# Sensor_module.net
KiCad netlist of a schematic drawn in EAGLE
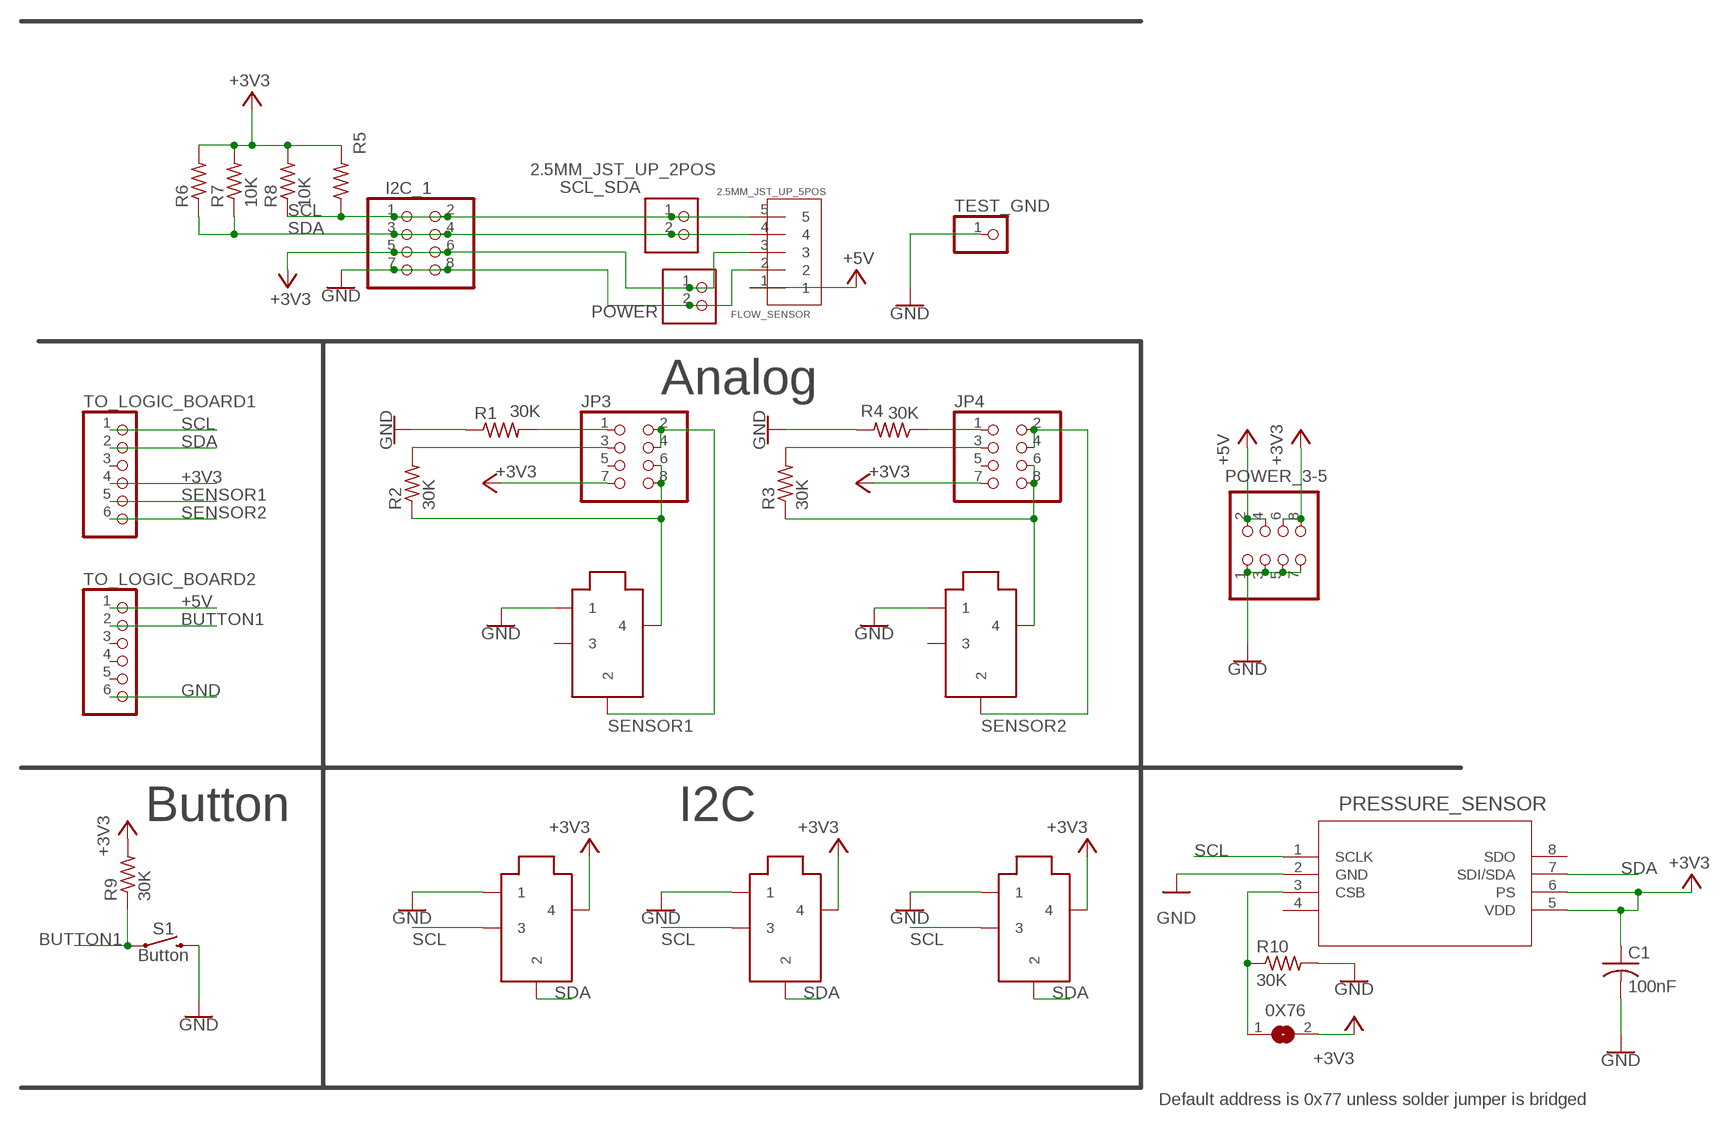
[diagram p0: schematic, sheet 1]

(export (version "E")
  (design (tool "Eeschema 10.0.6"))
  (components
    (comp (ref "0X76")
      (value "SJ")
      (footprint "eagle-import:SJ")
      (libsource (lib "eagle-import") (part "SJ"))
    )
    (comp (ref "ANALOG1")
      (value "AUDIOJACK_2.5MM_SMD")
      (footprint "eagle-import:AJ_2.5_SMD")
      (libsource (lib "eagle-import") (part "AUDIOJACK_2.5MM_SMD"))
    )
    (comp (ref "ANALOG2")
      (value "AUDIOJACK_2.5MM_SMD")
      (footprint "eagle-import:AJ_2.5_SMD")
      (libsource (lib "eagle-import") (part "AUDIOJACK_2.5MM_SMD"))
    )
    (comp (ref "C1")
      (value "100nF")
      (footprint "eagle-import:C1206")
      (libsource (lib "eagle-import") (part "C-USC1206"))
    )
    (comp (ref "FLOW_SENSOR")
      (value "2.5MM_JST_UP_5POS")
      (footprint "eagle-import:JST_5POS_2.5MM_UP")
      (libsource (lib "eagle-import") (part "2.5MM_JST_UP_5POS"))
    )
    (comp (ref "I2C_1")
      (value "PINHD-2X4")
      (footprint "eagle-import:2X04")
      (libsource (lib "eagle-import") (part "PINHD-2X4"))
    )
    (comp (ref "JP3")
      (value "PINHD-2X4")
      (footprint "eagle-import:2X04")
      (libsource (lib "eagle-import") (part "PINHD-2X4"))
    )
    (comp (ref "JP4")
      (value "PINHD-2X4")
      (footprint "eagle-import:2X04")
      (libsource (lib "eagle-import") (part "PINHD-2X4"))
    )
    (comp (ref "POWER")
      (value "2.5MM_JST_UP_2POS")
      (footprint "eagle-import:JST_2POS_2.5MM_UP")
      (libsource (lib "eagle-import") (part "2.5MM_JST_UP_2POS"))
    )
    (comp (ref "POWER_3-5")
      (value "PINHD-2X4")
      (footprint "eagle-import:2X04")
      (libsource (lib "eagle-import") (part "PINHD-2X4"))
    )
    (comp (ref "PRESSURE_SENSOR")
      (value "MS580302BA01-00")
      (footprint "eagle-import:MS5803-02BA01")
      (fields (field (name "MANUFACTURER_PART_NUMBER") "MS580302BA0100"))
      (libsource (lib "eagle-import") (part "MS580302BA01-00"))
    )
    (comp (ref "R1")
      (value "30K")
      (footprint "eagle-import:R1206")
      (libsource (lib "eagle-import") (part "R-US_R1206"))
    )
    (comp (ref "R2")
      (value "30K")
      (footprint "eagle-import:R1206")
      (libsource (lib "eagle-import") (part "R-US_R1206"))
    )
    (comp (ref "R3")
      (value "30K")
      (footprint "eagle-import:R1206")
      (libsource (lib "eagle-import") (part "R-US_R1206"))
    )
    (comp (ref "R4")
      (value "30K")
      (footprint "eagle-import:R1206")
      (libsource (lib "eagle-import") (part "R-US_R1206"))
    )
    (comp (ref "R5")
      (value "R-US_R1206")
      (footprint "eagle-import:R1206")
      (libsource (lib "eagle-import") (part "R-US_R1206"))
    )
    (comp (ref "R6")
      (value "R-US_R1206")
      (footprint "eagle-import:R1206")
      (libsource (lib "eagle-import") (part "R-US_R1206"))
    )
    (comp (ref "R7")
      (value "10K")
      (footprint "eagle-import:0204_7")
      (libsource (lib "eagle-import") (part "R-US_0204/7"))
    )
    (comp (ref "R8")
      (value "10K")
      (footprint "eagle-import:0204_7")
      (libsource (lib "eagle-import") (part "R-US_0204/7"))
    )
    (comp (ref "R9")
      (value "30K")
      (footprint "eagle-import:R1206")
      (libsource (lib "eagle-import") (part "R-US_R1206"))
    )
    (comp (ref "R10")
      (value "30K")
      (footprint "eagle-import:R1206")
      (libsource (lib "eagle-import") (part "R-US_R1206"))
    )
    (comp (ref "S1")
      (value "Button")
      (footprint "eagle-import:TACTILE_SWITCH_PTH_6.0MM")
      (libsource (lib "eagle-import") (part "MOMENTARY-SWITCH-SPST-PTH-6.0MM"))
    )
    (comp (ref "SCL_SDA")
      (value "2.5MM_JST_UP_2POS")
      (footprint "eagle-import:JST_2POS_2.5MM_UP")
      (libsource (lib "eagle-import") (part "2.5MM_JST_UP_2POS"))
    )
    (comp (ref "TEST_GND")
      (value "PINHD-1X1")
      (footprint "eagle-import:1X01")
      (libsource (lib "eagle-import") (part "PINHD-1X1"))
    )
    (comp (ref "TO_LOGIC_BOARD1")
      (value "PINHD-1X6CB")
      (footprint "eagle-import:1X06-CLEANBIG")
      (libsource (lib "eagle-import") (part "PINHD-1X6CB"))
    )
    (comp (ref "TO_LOGIC_BOARD2")
      (value "PINHD-1X6CB")
      (footprint "eagle-import:1X06-CLEANBIG")
      (libsource (lib "eagle-import") (part "PINHD-1X6CB"))
    )
    (comp (ref "U$1")
      (value "I2C")
      (footprint "eagle-import:AJ_2.5_SMD")
      (libsource (lib "eagle-import") (part "AUDIOJACK_2.5MM_SMD"))
    )
    (comp (ref "U$2")
      (value "I2C")
      (footprint "eagle-import:AJ_2.5_SMD")
      (libsource (lib "eagle-import") (part "AUDIOJACK_2.5MM_SMD"))
    )
    (comp (ref "U$5")
      (value "I2C")
      (footprint "eagle-import:AJ_2.5_SMD")
      (libsource (lib "eagle-import") (part "AUDIOJACK_2.5MM_SMD"))
    )
  )
  (nets
    (net (code "1") (name "+3V3") (class "Default")
      (node (ref "0X76") (pin "2") (pinfunction "2_2") (pintype "passive"))
      (node (ref "C1") (pin "1") (pinfunction "1_1") (pintype "passive"))
      (node (ref "FLOW_SENSOR") (pin "3") (pinfunction "3_3") (pintype "bidirectional"))
      (node (ref "I2C_1") (pin "5") (pinfunction "5_5") (pintype "passive"))
      (node (ref "I2C_1") (pin "6") (pinfunction "6_6") (pintype "passive"))
      (node (ref "JP3") (pin "7") (pinfunction "7_7") (pintype "passive"))
      (node (ref "JP4") (pin "7") (pinfunction "7_7") (pintype "passive"))
      (node (ref "POWER") (pin "1") (pinfunction "1_1") (pintype "bidirectional"))
      (node (ref "POWER_3-5") (pin "6") (pinfunction "6_6") (pintype "passive"))
      (node (ref "POWER_3-5") (pin "8") (pinfunction "8_8") (pintype "passive"))
      (node (ref "PRESSURE_SENSOR") (pin "5") (pinfunction "VDD_5") (pintype "power_in"))
      (node (ref "PRESSURE_SENSOR") (pin "6") (pinfunction "PS_6") (pintype "input"))
      (node (ref "R5") (pin "2") (pinfunction "2_2") (pintype "passive"))
      (node (ref "R6") (pin "2") (pinfunction "2_2") (pintype "passive"))
      (node (ref "R7") (pin "2") (pinfunction "2_2") (pintype "passive"))
      (node (ref "R8") (pin "2") (pinfunction "2_2") (pintype "passive"))
      (node (ref "R9") (pin "2") (pinfunction "2_2") (pintype "passive"))
      (node (ref "TO_LOGIC_BOARD1") (pin "4") (pinfunction "4_4") (pintype "passive"))
      (node (ref "U$1") (pin "4") (pinfunction "4_4") (pintype "bidirectional"))
      (node (ref "U$2") (pin "4") (pinfunction "4_4") (pintype "bidirectional"))
      (node (ref "U$5") (pin "4") (pinfunction "4_4") (pintype "bidirectional"))
    )
    (net (code "2") (name "+5V") (class "Default")
      (node (ref "FLOW_SENSOR") (pin "1") (pinfunction "1_1") (pintype "bidirectional"))
      (node (ref "POWER_3-5") (pin "2") (pinfunction "2_2") (pintype "passive"))
      (node (ref "POWER_3-5") (pin "4") (pinfunction "4_4") (pintype "passive"))
      (node (ref "TO_LOGIC_BOARD2") (pin "1") (pinfunction "1_1") (pintype "passive"))
    )
    (net (code "3") (name "/BUTTON1") (class "Default")
      (node (ref "R9") (pin "1") (pinfunction "1_1") (pintype "passive"))
      (node (ref "S1") (pin "1") (pinfunction "1_1") (pintype "passive"))
      (node (ref "TO_LOGIC_BOARD2") (pin "2") (pinfunction "2_2") (pintype "passive"))
    )
    (net (code "4") (name "/SCL") (class "Default")
      (node (ref "FLOW_SENSOR") (pin "5") (pinfunction "5_5") (pintype "bidirectional"))
      (node (ref "I2C_1") (pin "1") (pinfunction "1_1") (pintype "passive"))
      (node (ref "I2C_1") (pin "2") (pinfunction "2_2") (pintype "passive"))
      (node (ref "PRESSURE_SENSOR") (pin "1") (pinfunction "SCLK_1") (pintype "input"))
      (node (ref "R5") (pin "1") (pinfunction "1_1") (pintype "passive"))
      (node (ref "R8") (pin "1") (pinfunction "1_1") (pintype "passive"))
      (node (ref "SCL_SDA") (pin "1") (pinfunction "1_1") (pintype "bidirectional"))
      (node (ref "TO_LOGIC_BOARD1") (pin "1") (pinfunction "1_1") (pintype "passive"))
      (node (ref "U$1") (pin "3") (pinfunction "3_3") (pintype "bidirectional"))
      (node (ref "U$2") (pin "3") (pinfunction "3_3") (pintype "bidirectional"))
      (node (ref "U$5") (pin "3") (pinfunction "3_3") (pintype "bidirectional"))
    )
    (net (code "5") (name "/SDA") (class "Default")
      (node (ref "FLOW_SENSOR") (pin "4") (pinfunction "4_4") (pintype "bidirectional"))
      (node (ref "I2C_1") (pin "3") (pinfunction "3_3") (pintype "passive"))
      (node (ref "I2C_1") (pin "4") (pinfunction "4_4") (pintype "passive"))
      (node (ref "PRESSURE_SENSOR") (pin "7") (pinfunction "SDI/SDA_7") (pintype "input"))
      (node (ref "R6") (pin "1") (pinfunction "1_1") (pintype "passive"))
      (node (ref "R7") (pin "1") (pinfunction "1_1") (pintype "passive"))
      (node (ref "SCL_SDA") (pin "2") (pinfunction "2_2") (pintype "bidirectional"))
      (node (ref "TO_LOGIC_BOARD1") (pin "2") (pinfunction "2_2") (pintype "passive"))
      (node (ref "U$1") (pin "2") (pinfunction "2_2") (pintype "bidirectional"))
      (node (ref "U$2") (pin "2") (pinfunction "2_2") (pintype "bidirectional"))
      (node (ref "U$5") (pin "2") (pinfunction "2_2") (pintype "bidirectional"))
    )
    (net (code "6") (name "/SENSOR1") (class "Default")
      (node (ref "ANALOG1") (pin "2") (pinfunction "2_2") (pintype "bidirectional"))
      (node (ref "JP3") (pin "2") (pinfunction "2_2") (pintype "passive"))
      (node (ref "JP3") (pin "4") (pinfunction "4_4") (pintype "passive"))
      (node (ref "TO_LOGIC_BOARD1") (pin "5") (pinfunction "5_5") (pintype "passive"))
    )
    (net (code "7") (name "/SENSOR2") (class "Default")
      (node (ref "ANALOG2") (pin "2") (pinfunction "2_2") (pintype "bidirectional"))
      (node (ref "JP4") (pin "2") (pinfunction "2_2") (pintype "passive"))
      (node (ref "JP4") (pin "4") (pinfunction "4_4") (pintype "passive"))
      (node (ref "TO_LOGIC_BOARD1") (pin "6") (pinfunction "6_6") (pintype "passive"))
    )
    (net (code "8") (name "GND") (class "Default")
      (node (ref "ANALOG1") (pin "1") (pinfunction "1_1") (pintype "bidirectional"))
      (node (ref "ANALOG2") (pin "1") (pinfunction "1_1") (pintype "bidirectional"))
      (node (ref "C1") (pin "2") (pinfunction "2_2") (pintype "passive"))
      (node (ref "FLOW_SENSOR") (pin "2") (pinfunction "2_2") (pintype "bidirectional"))
      (node (ref "I2C_1") (pin "7") (pinfunction "7_7") (pintype "passive"))
      (node (ref "I2C_1") (pin "8") (pinfunction "8_8") (pintype "passive"))
      (node (ref "POWER") (pin "2") (pinfunction "2_2") (pintype "bidirectional"))
      (node (ref "POWER_3-5") (pin "1") (pinfunction "1_1") (pintype "passive"))
      (node (ref "POWER_3-5") (pin "3") (pinfunction "3_3") (pintype "passive"))
      (node (ref "POWER_3-5") (pin "5") (pinfunction "5_5") (pintype "passive"))
      (node (ref "POWER_3-5") (pin "7") (pinfunction "7_7") (pintype "passive"))
      (node (ref "PRESSURE_SENSOR") (pin "2") (pinfunction "GND_2") (pintype "passive"))
      (node (ref "R1") (pin "1") (pinfunction "1_1") (pintype "passive"))
      (node (ref "R10") (pin "2") (pinfunction "2_2") (pintype "passive"))
      (node (ref "R4") (pin "2") (pinfunction "2_2") (pintype "passive"))
      (node (ref "S1") (pin "3") (pinfunction "2_3") (pintype "passive"))
      (node (ref "TEST_GND") (pin "1") (pinfunction "1_1") (pintype "passive"))
      (node (ref "TO_LOGIC_BOARD2") (pin "6") (pinfunction "6_6") (pintype "passive"))
      (node (ref "U$1") (pin "1") (pinfunction "1_1") (pintype "bidirectional"))
      (node (ref "U$2") (pin "1") (pinfunction "1_1") (pintype "bidirectional"))
      (node (ref "U$5") (pin "1") (pinfunction "1_1") (pintype "bidirectional"))
    )
    (net (code "9") (name "Net-(ANALOG1-Pad4)") (class "Default")
      (node (ref "ANALOG1") (pin "4") (pinfunction "4_4") (pintype "bidirectional"))
      (node (ref "JP3") (pin "6") (pinfunction "6_6") (pintype "passive"))
      (node (ref "JP3") (pin "8") (pinfunction "8_8") (pintype "passive"))
      (node (ref "R2") (pin "1") (pinfunction "1_1") (pintype "passive"))
    )
    (net (code "10") (name "Net-(ANALOG2-Pad4)") (class "Default")
      (node (ref "ANALOG2") (pin "4") (pinfunction "4_4") (pintype "bidirectional"))
      (node (ref "JP4") (pin "6") (pinfunction "6_6") (pintype "passive"))
      (node (ref "JP4") (pin "8") (pinfunction "8_8") (pintype "passive"))
      (node (ref "R3") (pin "1") (pinfunction "1_1") (pintype "passive"))
    )
    (net (code "11") (name "Net-(JP3-Pad1)") (class "Default")
      (node (ref "JP3") (pin "1") (pinfunction "1_1") (pintype "passive"))
      (node (ref "R1") (pin "2") (pinfunction "2_2") (pintype "passive"))
    )
    (net (code "12") (name "Net-(JP3-Pad3)") (class "Default")
      (node (ref "JP3") (pin "3") (pinfunction "3_3") (pintype "passive"))
      (node (ref "R2") (pin "2") (pinfunction "2_2") (pintype "passive"))
    )
    (net (code "13") (name "Net-(JP4-Pad1)") (class "Default")
      (node (ref "JP4") (pin "1") (pinfunction "1_1") (pintype "passive"))
      (node (ref "R4") (pin "1") (pinfunction "1_1") (pintype "passive"))
    )
    (net (code "14") (name "Net-(JP4-Pad3)") (class "Default")
      (node (ref "JP4") (pin "3") (pinfunction "3_3") (pintype "passive"))
      (node (ref "R3") (pin "2") (pinfunction "2_2") (pintype "passive"))
    )
    (net (code "15") (name "Net-(PRESSURE_SENSOR-CSB)") (class "Default")
      (node (ref "0X76") (pin "1") (pinfunction "1_1") (pintype "passive"))
      (node (ref "PRESSURE_SENSOR") (pin "3") (pinfunction "CSB_3") (pintype "input"))
      (node (ref "R10") (pin "1") (pinfunction "1_1") (pintype "passive"))
    )
    (net (code "16") (name "unconnected-(ANALOG1-Pad3)") (class "Default")
      (node (ref "ANALOG1") (pin "3") (pinfunction "3_3") (pintype "bidirectional"))
    )
    (net (code "17") (name "unconnected-(ANALOG2-Pad3)") (class "Default")
      (node (ref "ANALOG2") (pin "3") (pinfunction "3_3") (pintype "bidirectional"))
    )
    (net (code "18") (name "unconnected-(JP3-Pad5)") (class "Default")
      (node (ref "JP3") (pin "5") (pinfunction "5_5") (pintype "passive"))
    )
    (net (code "19") (name "unconnected-(JP4-Pad5)") (class "Default")
      (node (ref "JP4") (pin "5") (pinfunction "5_5") (pintype "passive"))
    )
    (net (code "20") (name "unconnected-(PRESSURE_SENSOR-NC-Pad4)") (class "Default")
      (node (ref "PRESSURE_SENSOR") (pin "4") (pinfunction "NC_4") (pintype "no_connect"))
    )
    (net (code "21") (name "unconnected-(PRESSURE_SENSOR-SDO-Pad8)") (class "Default")
      (node (ref "PRESSURE_SENSOR") (pin "8") (pinfunction "SDO_8") (pintype "output"))
    )
    (net (code "22") (name "unconnected-(TO_LOGIC_BOARD1-Pad3)") (class "Default")
      (node (ref "TO_LOGIC_BOARD1") (pin "3") (pinfunction "3_3") (pintype "passive"))
    )
    (net (code "23") (name "unconnected-(TO_LOGIC_BOARD2-Pad3)") (class "Default")
      (node (ref "TO_LOGIC_BOARD2") (pin "3") (pinfunction "3_3") (pintype "passive"))
    )
    (net (code "24") (name "unconnected-(TO_LOGIC_BOARD2-Pad4)") (class "Default")
      (node (ref "TO_LOGIC_BOARD2") (pin "4") (pinfunction "4_4") (pintype "passive"))
    )
    (net (code "25") (name "unconnected-(TO_LOGIC_BOARD2-Pad5)") (class "Default")
      (node (ref "TO_LOGIC_BOARD2") (pin "5") (pinfunction "5_5") (pintype "passive"))
    )
  )
)
